# Custom_Board_2.net
KiCad netlist of a schematic drawn in EAGLE
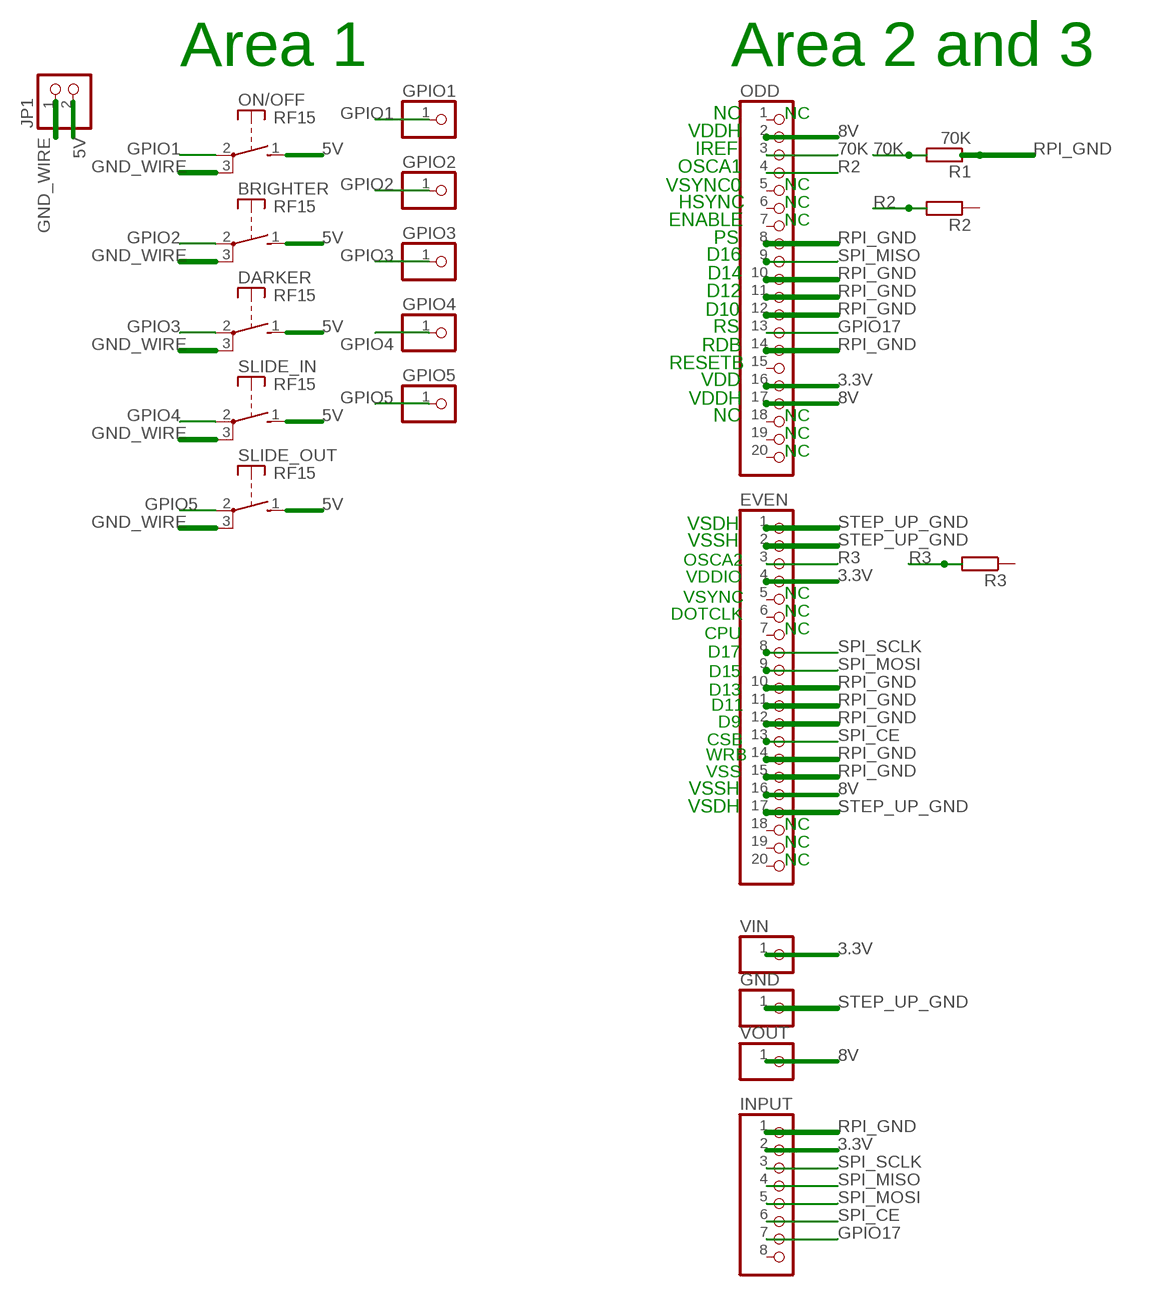
[diagram p0: schematic, sheet 1]

(export (version "E")
  (design (tool "Eeschema 10.0.6"))
  (components
    (comp (ref "BRIGHTER")
      (value "RF15")
      (footprint "eagle-import:RF15")
      (libsource (lib "eagle-import") (part "RF15"))
    )
    (comp (ref "DARKER")
      (value "RF15")
      (footprint "eagle-import:RF15")
      (libsource (lib "eagle-import") (part "RF15"))
    )
    (comp (ref "EVEN")
      (value "PINHD-1X20")
      (footprint "eagle-import:1X20")
      (libsource (lib "eagle-import") (part "PINHD-1X20"))
    )
    (comp (ref "GND")
      (value "PINHD-1X1")
      (footprint "eagle-import:1X01")
      (libsource (lib "eagle-import") (part "PINHD-1X1"))
    )
    (comp (ref "GPIO1")
      (value "PINHD-1X1")
      (footprint "eagle-import:1X01")
      (libsource (lib "eagle-import") (part "PINHD-1X1"))
    )
    (comp (ref "GPIO2")
      (value "PINHD-1X1")
      (footprint "eagle-import:1X01")
      (libsource (lib "eagle-import") (part "PINHD-1X1"))
    )
    (comp (ref "GPIO3")
      (value "PINHD-1X1")
      (footprint "eagle-import:1X01")
      (libsource (lib "eagle-import") (part "PINHD-1X1"))
    )
    (comp (ref "GPIO4")
      (value "PINHD-1X1")
      (footprint "eagle-import:1X01")
      (libsource (lib "eagle-import") (part "PINHD-1X1"))
    )
    (comp (ref "GPIO5")
      (value "PINHD-1X1")
      (footprint "eagle-import:1X01")
      (libsource (lib "eagle-import") (part "PINHD-1X1"))
    )
    (comp (ref "INPUT")
      (value "PINHD-1X8")
      (footprint "eagle-import:1X08")
      (libsource (lib "eagle-import") (part "PINHD-1X8"))
    )
    (comp (ref "JP1")
      (value "PINHD-1X2")
      (footprint "eagle-import:1X02")
      (libsource (lib "eagle-import") (part "PINHD-1X2"))
    )
    (comp (ref "ODD")
      (value "PINHD-1X20")
      (footprint "eagle-import:1X20")
      (libsource (lib "eagle-import") (part "PINHD-1X20"))
    )
    (comp (ref "ON/OFF")
      (value "RF15")
      (footprint "eagle-import:RF15")
      (libsource (lib "eagle-import") (part "RF15"))
    )
    (comp (ref "R1")
      (value "70K")
      (footprint "eagle-import:0204_7")
      (libsource (lib "eagle-import") (part "R-EU_0204/7"))
    )
    (comp (ref "R2")
      (value "R-EU_0204/7")
      (footprint "eagle-import:0204_7")
      (libsource (lib "eagle-import") (part "R-EU_0204/7"))
    )
    (comp (ref "R3")
      (value "R-EU_0204/7")
      (footprint "eagle-import:0204_7")
      (libsource (lib "eagle-import") (part "R-EU_0204/7"))
    )
    (comp (ref "SLIDE_IN")
      (value "RF15")
      (footprint "eagle-import:RF15")
      (libsource (lib "eagle-import") (part "RF15"))
    )
    (comp (ref "SLIDE_OUT")
      (value "RF15")
      (footprint "eagle-import:RF15")
      (libsource (lib "eagle-import") (part "RF15"))
    )
    (comp (ref "VIN")
      (value "PINHD-1X1")
      (footprint "eagle-import:1X01")
      (libsource (lib "eagle-import") (part "PINHD-1X1"))
    )
    (comp (ref "VOUT")
      (value "PINHD-1X1")
      (footprint "eagle-import:1X01")
      (libsource (lib "eagle-import") (part "PINHD-1X1"))
    )
  )
  (nets
    (net (code "1") (name "/3.3V") (class "Default")
      (node (ref "EVEN") (pin "4") (pinfunction "4_4") (pintype "passive"))
      (node (ref "INPUT") (pin "2") (pinfunction "2_2") (pintype "passive"))
      (node (ref "ODD") (pin "16") (pinfunction "16_16") (pintype "passive"))
      (node (ref "VIN") (pin "1") (pinfunction "1_1") (pintype "passive"))
    )
    (net (code "2") (name "/5V") (class "Default")
      (node (ref "BRIGHTER") (pin "1") (pinfunction "S_1") (pintype "passive"))
      (node (ref "DARKER") (pin "1") (pinfunction "S_1") (pintype "passive"))
      (node (ref "JP1") (pin "2") (pinfunction "2_2") (pintype "passive"))
      (node (ref "ON/OFF") (pin "1") (pinfunction "S_1") (pintype "passive"))
      (node (ref "SLIDE_IN") (pin "1") (pinfunction "S_1") (pintype "passive"))
      (node (ref "SLIDE_OUT") (pin "1") (pinfunction "S_1") (pintype "passive"))
    )
    (net (code "3") (name "/8V") (class "Default")
      (node (ref "EVEN") (pin "16") (pinfunction "16_16") (pintype "passive"))
      (node (ref "ODD") (pin "17") (pinfunction "17_17") (pintype "passive"))
      (node (ref "ODD") (pin "2") (pinfunction "2_2") (pintype "passive"))
      (node (ref "VOUT") (pin "1") (pinfunction "1_1") (pintype "passive"))
    )
    (net (code "4") (name "/70K") (class "Default")
      (node (ref "ODD") (pin "3") (pinfunction "3_3") (pintype "passive"))
      (node (ref "R1") (pin "2") (pinfunction "2_2") (pintype "passive"))
    )
    (net (code "5") (name "/GND_WIRE") (class "Default")
      (node (ref "BRIGHTER") (pin "3") (pinfunction "P_3") (pintype "passive"))
      (node (ref "DARKER") (pin "3") (pinfunction "P_3") (pintype "passive"))
      (node (ref "JP1") (pin "1") (pinfunction "1_1") (pintype "passive"))
      (node (ref "ON/OFF") (pin "3") (pinfunction "P_3") (pintype "passive"))
      (node (ref "SLIDE_IN") (pin "3") (pinfunction "P_3") (pintype "passive"))
      (node (ref "SLIDE_OUT") (pin "3") (pinfunction "P_3") (pintype "passive"))
    )
    (net (code "6") (name "/GPIO1") (class "Default")
      (node (ref "GPIO1") (pin "1") (pinfunction "1_1") (pintype "passive"))
      (node (ref "ON/OFF") (pin "2") (pinfunction "P_2") (pintype "passive"))
    )
    (net (code "7") (name "/GPIO2") (class "Default")
      (node (ref "BRIGHTER") (pin "2") (pinfunction "P_2") (pintype "passive"))
      (node (ref "GPIO2") (pin "1") (pinfunction "1_1") (pintype "passive"))
    )
    (net (code "8") (name "/GPIO3") (class "Default")
      (node (ref "DARKER") (pin "2") (pinfunction "P_2") (pintype "passive"))
      (node (ref "GPIO3") (pin "1") (pinfunction "1_1") (pintype "passive"))
    )
    (net (code "9") (name "/GPIO4") (class "Default")
      (node (ref "GPIO4") (pin "1") (pinfunction "1_1") (pintype "passive"))
      (node (ref "SLIDE_IN") (pin "2") (pinfunction "P_2") (pintype "passive"))
    )
    (net (code "10") (name "/GPIO5") (class "Default")
      (node (ref "GPIO5") (pin "1") (pinfunction "1_1") (pintype "passive"))
      (node (ref "SLIDE_OUT") (pin "2") (pinfunction "P_2") (pintype "passive"))
    )
    (net (code "11") (name "/GPIO17") (class "Default")
      (node (ref "INPUT") (pin "7") (pinfunction "7_7") (pintype "passive"))
      (node (ref "ODD") (pin "13") (pinfunction "13_13") (pintype "passive"))
    )
    (net (code "12") (name "/R2") (class "Default")
      (node (ref "ODD") (pin "4") (pinfunction "4_4") (pintype "passive"))
      (node (ref "R2") (pin "2") (pinfunction "2_2") (pintype "passive"))
    )
    (net (code "13") (name "/R3") (class "Default")
      (node (ref "EVEN") (pin "3") (pinfunction "3_3") (pintype "passive"))
      (node (ref "R3") (pin "2") (pinfunction "2_2") (pintype "passive"))
    )
    (net (code "14") (name "/RPI_GND") (class "Default")
      (node (ref "EVEN") (pin "10") (pinfunction "10_10") (pintype "passive"))
      (node (ref "EVEN") (pin "11") (pinfunction "11_11") (pintype "passive"))
      (node (ref "EVEN") (pin "12") (pinfunction "12_12") (pintype "passive"))
      (node (ref "EVEN") (pin "14") (pinfunction "14_14") (pintype "passive"))
      (node (ref "EVEN") (pin "15") (pinfunction "15_15") (pintype "passive"))
      (node (ref "INPUT") (pin "1") (pinfunction "1_1") (pintype "passive"))
      (node (ref "ODD") (pin "10") (pinfunction "10_10") (pintype "passive"))
      (node (ref "ODD") (pin "11") (pinfunction "11_11") (pintype "passive"))
      (node (ref "ODD") (pin "12") (pinfunction "12_12") (pintype "passive"))
      (node (ref "ODD") (pin "14") (pinfunction "14_14") (pintype "passive"))
      (node (ref "ODD") (pin "8") (pinfunction "8_8") (pintype "passive"))
      (node (ref "R1") (pin "1") (pinfunction "1_1") (pintype "passive"))
    )
    (net (code "15") (name "/SPI_CE") (class "Default")
      (node (ref "EVEN") (pin "13") (pinfunction "13_13") (pintype "passive"))
      (node (ref "INPUT") (pin "6") (pinfunction "6_6") (pintype "passive"))
    )
    (net (code "16") (name "/SPI_MISO") (class "Default")
      (node (ref "INPUT") (pin "4") (pinfunction "4_4") (pintype "passive"))
      (node (ref "ODD") (pin "9") (pinfunction "9_9") (pintype "passive"))
    )
    (net (code "17") (name "/SPI_MOSI") (class "Default")
      (node (ref "EVEN") (pin "9") (pinfunction "9_9") (pintype "passive"))
      (node (ref "INPUT") (pin "5") (pinfunction "5_5") (pintype "passive"))
    )
    (net (code "18") (name "/SPI_SCLK") (class "Default")
      (node (ref "EVEN") (pin "8") (pinfunction "8_8") (pintype "passive"))
      (node (ref "INPUT") (pin "3") (pinfunction "3_3") (pintype "passive"))
    )
    (net (code "19") (name "/STEP_UP_GND") (class "Default")
      (node (ref "EVEN") (pin "1") (pinfunction "1_1") (pintype "passive"))
      (node (ref "EVEN") (pin "17") (pinfunction "17_17") (pintype "passive"))
      (node (ref "EVEN") (pin "2") (pinfunction "2_2") (pintype "passive"))
      (node (ref "GND") (pin "1") (pinfunction "1_1") (pintype "passive"))
    )
    (net (code "20") (name "unconnected-(EVEN-Pad5)") (class "Default")
      (node (ref "EVEN") (pin "5") (pinfunction "5_5") (pintype "passive"))
    )
    (net (code "21") (name "unconnected-(EVEN-Pad6)") (class "Default")
      (node (ref "EVEN") (pin "6") (pinfunction "6_6") (pintype "passive"))
    )
    (net (code "22") (name "unconnected-(EVEN-Pad7)") (class "Default")
      (node (ref "EVEN") (pin "7") (pinfunction "7_7") (pintype "passive"))
    )
    (net (code "23") (name "unconnected-(EVEN-Pad18)") (class "Default")
      (node (ref "EVEN") (pin "18") (pinfunction "18_18") (pintype "passive"))
    )
    (net (code "24") (name "unconnected-(EVEN-Pad19)") (class "Default")
      (node (ref "EVEN") (pin "19") (pinfunction "19_19") (pintype "passive"))
    )
    (net (code "25") (name "unconnected-(EVEN-Pad20)") (class "Default")
      (node (ref "EVEN") (pin "20") (pinfunction "20_20") (pintype "passive"))
    )
    (net (code "26") (name "unconnected-(INPUT-Pad8)") (class "Default")
      (node (ref "INPUT") (pin "8") (pinfunction "8_8") (pintype "passive"))
    )
    (net (code "27") (name "unconnected-(ODD-Pad1)") (class "Default")
      (node (ref "ODD") (pin "1") (pinfunction "1_1") (pintype "passive"))
    )
    (net (code "28") (name "unconnected-(ODD-Pad5)") (class "Default")
      (node (ref "ODD") (pin "5") (pinfunction "5_5") (pintype "passive"))
    )
    (net (code "29") (name "unconnected-(ODD-Pad6)") (class "Default")
      (node (ref "ODD") (pin "6") (pinfunction "6_6") (pintype "passive"))
    )
    (net (code "30") (name "unconnected-(ODD-Pad7)") (class "Default")
      (node (ref "ODD") (pin "7") (pinfunction "7_7") (pintype "passive"))
    )
    (net (code "31") (name "unconnected-(ODD-Pad15)") (class "Default")
      (node (ref "ODD") (pin "15") (pinfunction "15_15") (pintype "passive"))
    )
    (net (code "32") (name "unconnected-(ODD-Pad18)") (class "Default")
      (node (ref "ODD") (pin "18") (pinfunction "18_18") (pintype "passive"))
    )
    (net (code "33") (name "unconnected-(ODD-Pad19)") (class "Default")
      (node (ref "ODD") (pin "19") (pinfunction "19_19") (pintype "passive"))
    )
    (net (code "34") (name "unconnected-(ODD-Pad20)") (class "Default")
      (node (ref "ODD") (pin "20") (pinfunction "20_20") (pintype "passive"))
    )
    (net (code "35") (name "unconnected-(R2-Pad1)") (class "Default")
      (node (ref "R2") (pin "1") (pinfunction "1_1") (pintype "passive"))
    )
    (net (code "36") (name "unconnected-(R3-Pad1)") (class "Default")
      (node (ref "R3") (pin "1") (pinfunction "1_1") (pintype "passive"))
    )
  )
)
